# wo_ek.net
KiCad netlist of a schematic drawn in EAGLE
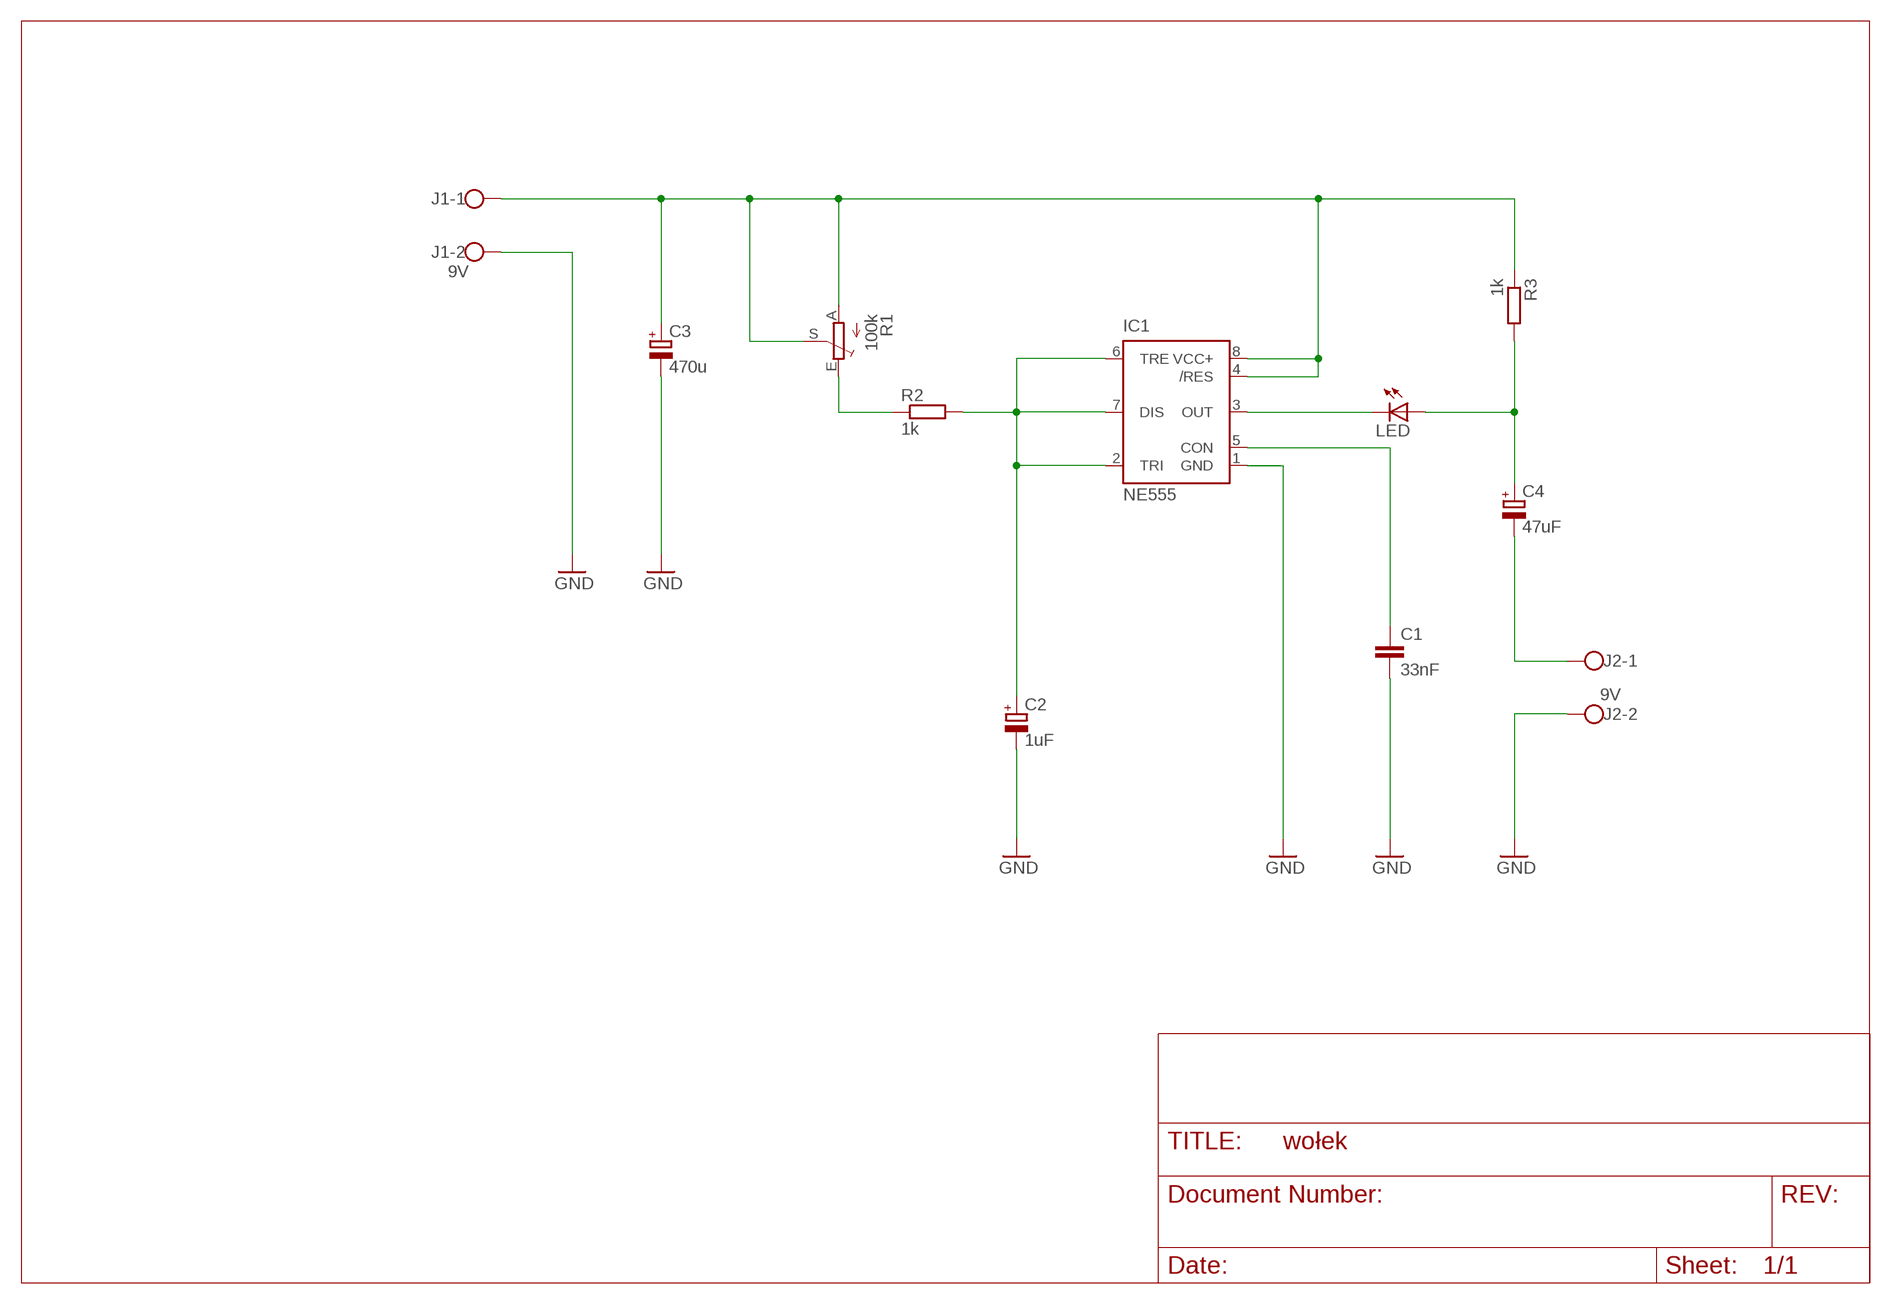
[diagram p0: schematic, sheet 1]

(export (version "E")
  (design (tool "Eeschema 10.0.6"))
  (components
    (comp (ref "C1")
      (value "33nF")
      (footprint "eagle-import:C1206K")
      (libsource (lib "eagle-import") (part "C-EUC1206K"))
    )
    (comp (ref "C2")
      (value "1uF")
      (footprint "eagle-import:E5-8,5")
      (libsource (lib "eagle-import") (part "CPOL-EUE5-8.5"))
    )
    (comp (ref "C3")
      (value "470u")
      (footprint "eagle-import:E7,5-16")
      (libsource (lib "eagle-import") (part "CPOL-EUE7.5-16"))
    )
    (comp (ref "C4")
      (value "47uF")
      (footprint "eagle-import:E5-8,5")
      (libsource (lib "eagle-import") (part "CPOL-EUE5-8.5"))
    )
    (comp (ref "IC1")
      (value "NE555")
      (footprint "eagle-import:DIL-08")
      (fields (field (name "MF") "Arrow Electronics") (field (name "MPN") "NE555N"))
      (libsource (lib "eagle-import") (part "NE555"))
    )
    (comp (ref "J1")
      (value "9V")
      (footprint "eagle-import:W237-102")
      (fields (field (name "MPN") "237-102"))
      (libsource (lib "eagle-import") (part "W237-102"))
    )
    (comp (ref "J2")
      (value "9V")
      (footprint "eagle-import:W237-102")
      (fields (field (name "MPN") "237-102"))
      (libsource (lib "eagle-import") (part "W237-102"))
    )
    (comp (ref "LED")
      (value "LED_LED3MM")
      (footprint "eagle-import:LED_LED3MM")
      (libsource (lib "eagle-import") (part "LED_LED3MM"))
    )
    (comp (ref "R1")
      (value "100k")
      (footprint "eagle-import:CA6V")
      (libsource (lib "eagle-import") (part "TRIM_EU-CA6V"))
    )
    (comp (ref "R2")
      (value "1k")
      (footprint "eagle-import:R1210W")
      (libsource (lib "eagle-import") (part "R-EU_R1210W"))
    )
    (comp (ref "R3")
      (value "1k")
      (footprint "eagle-import:R1210W")
      (libsource (lib "eagle-import") (part "R-EU_R1210W"))
    )
  )
  (nets
    (net (code "1") (name "GND") (class "Default")
      (node (ref "C1") (pin "2") (pinfunction "2_2") (pintype "passive"))
      (node (ref "C2") (pin "-") (pinfunction "-_-") (pintype "passive"))
      (node (ref "C3") (pin "-") (pinfunction "-_-") (pintype "passive"))
      (node (ref "IC1") (pin "1") (pinfunction "GND_1") (pintype "power_in"))
      (node (ref "J1") (pin "2") (pinfunction "KL_2") (pintype "passive"))
      (node (ref "J2") (pin "2") (pinfunction "KL_2") (pintype "passive"))
    )
    (net (code "2") (name "Net-(C4-Pad+)") (class "Default")
      (node (ref "C4") (pin "+") (pinfunction "+_+") (pintype "passive"))
      (node (ref "LED") (pin "A") (pinfunction "A_A") (pintype "passive"))
      (node (ref "R3") (pin "2") (pinfunction "2_2") (pintype "passive"))
    )
    (net (code "3") (name "Net-(IC1-CON)") (class "Default")
      (node (ref "C1") (pin "1") (pinfunction "1_1") (pintype "passive"))
      (node (ref "IC1") (pin "5") (pinfunction "CON_5") (pintype "input"))
    )
    (net (code "4") (name "Net-(IC1-DIS)") (class "Default")
      (node (ref "C2") (pin "+") (pinfunction "+_+") (pintype "passive"))
      (node (ref "IC1") (pin "2") (pinfunction "TRI_2") (pintype "input"))
      (node (ref "IC1") (pin "6") (pinfunction "TRE_6") (pintype "input"))
      (node (ref "IC1") (pin "7") (pinfunction "DIS_7") (pintype "input"))
      (node (ref "R2") (pin "2") (pinfunction "2_2") (pintype "passive"))
    )
    (net (code "5") (name "Net-(IC1-OUT)") (class "Default")
      (node (ref "IC1") (pin "3") (pinfunction "OUT_3") (pintype "output"))
      (node (ref "LED") (pin "K") (pinfunction "C_K") (pintype "passive"))
    )
    (net (code "6") (name "Net-(IC1-VCC+)") (class "Default")
      (node (ref "C3") (pin "+") (pinfunction "+_+") (pintype "passive"))
      (node (ref "IC1") (pin "4") (pinfunction "/RES_4") (pintype "input"))
      (node (ref "IC1") (pin "8") (pinfunction "VCC+_8") (pintype "power_in"))
      (node (ref "J1") (pin "1") (pinfunction "KL_1") (pintype "passive"))
      (node (ref "R1") (pin "A") (pinfunction "A_A") (pintype "passive"))
      (node (ref "R1") (pin "S") (pinfunction "S_S") (pintype "passive"))
      (node (ref "R3") (pin "1") (pinfunction "1_1") (pintype "passive"))
    )
    (net (code "7") (name "Net-(J2A-KL)") (class "Default")
      (node (ref "C4") (pin "-") (pinfunction "-_-") (pintype "passive"))
      (node (ref "J2") (pin "1") (pinfunction "KL_1") (pintype "passive"))
    )
    (net (code "8") (name "Net-(R1-PadE)") (class "Default")
      (node (ref "R1") (pin "E") (pinfunction "E_E") (pintype "passive"))
      (node (ref "R2") (pin "1") (pinfunction "1_1") (pintype "passive"))
    )
  )
)
